# OMD_UWB.net
KiCad netlist of a schematic drawn in Altium Designer
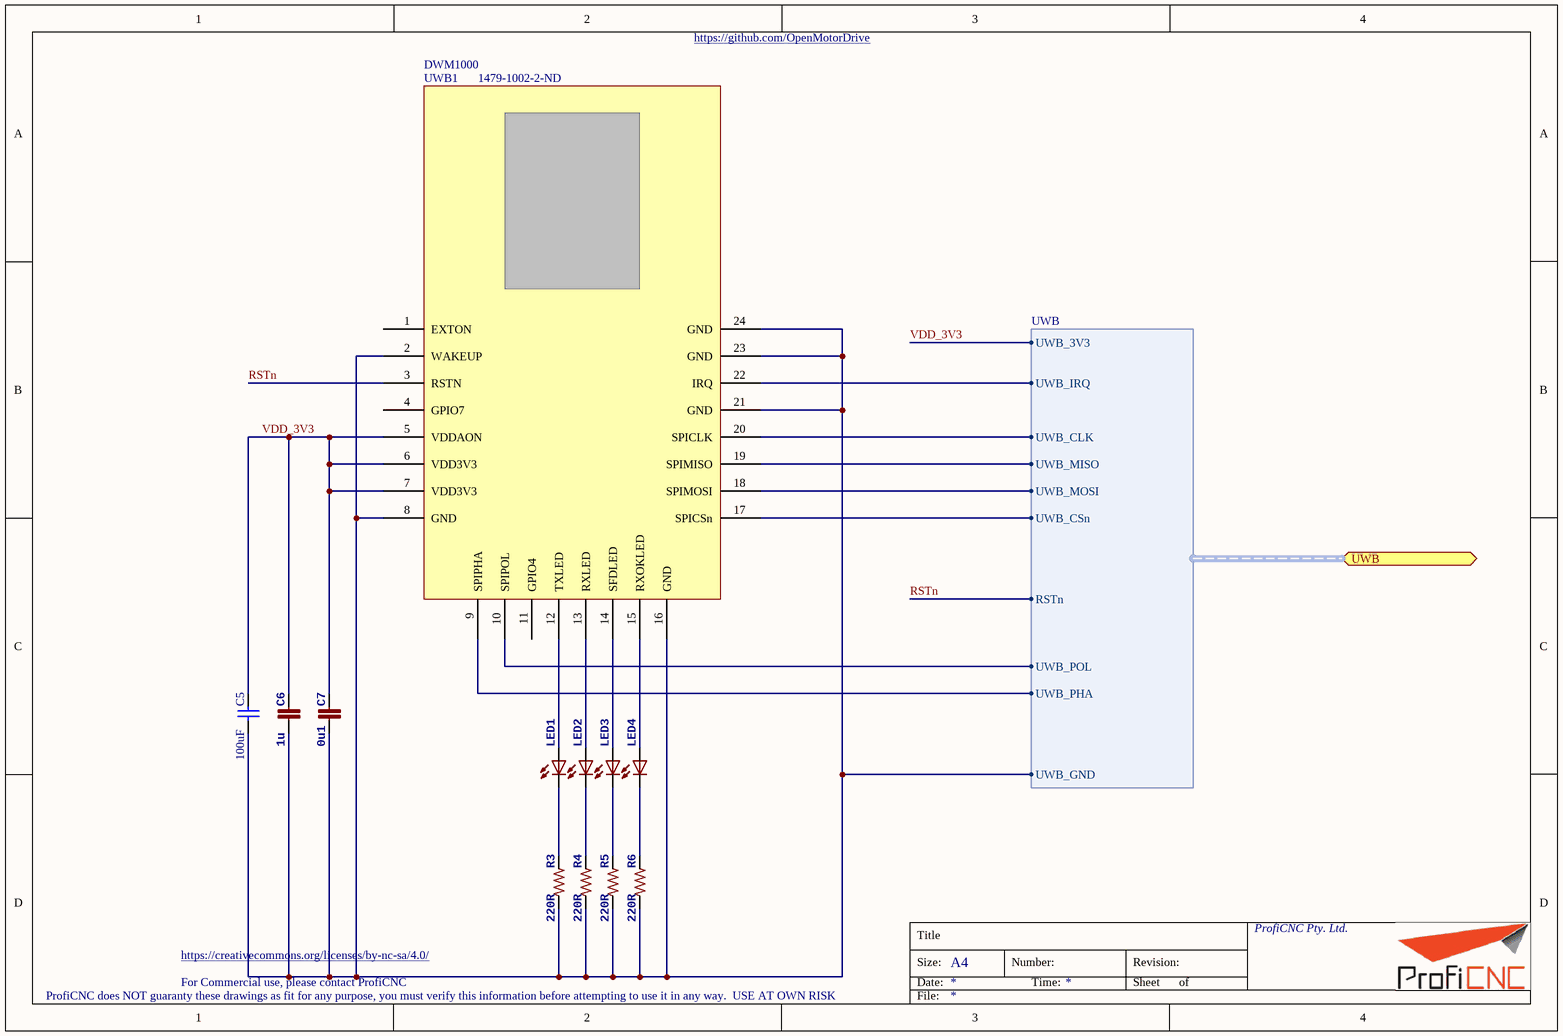
[diagram p0: OMD_UWB.SchDoc]

(export (version "E")
  (design (tool "Eeschema 10.0.6"))
  (components
    (comp (ref "C5")
      (value "100uF")
      (footprint "C0805")
      (fields (field (name "Comment") "GRM21BR60G107ME15L"))
      (libsource (lib "OMD") (part "Capacitor"))
    )
    (comp (ref "C6")
      (value "1u")
      (footprint "0201-cap")
      (description "CAP CER 1UF 6.3V X5R 0201")
      (libsource (lib "OMD") (part "CAP0603"))
    )
    (comp (ref "C7")
      (value "0u1")
      (footprint "0201-cap")
      (description "CAP CER 0.1UF 16V Y5V 0402")
      (libsource (lib "OMD") (part "CAP0402"))
    )
    (comp (ref "LED1")
      (value "AMBER")
      (footprint "0603-LED")
      (description "LED 1.6X0.8 DOME ORN CLEAR SMD")
      (libsource (lib "OMD") (part "LED0603"))
    )
    (comp (ref "LED2")
      (value "AMBER")
      (footprint "0603-LED")
      (description "LED 1.6X0.8 DOME ORN CLEAR SMD")
      (libsource (lib "OMD") (part "LED0603"))
    )
    (comp (ref "LED3")
      (value "AMBER")
      (footprint "0603-LED")
      (description "LED 1.6X0.8 DOME ORN CLEAR SMD")
      (libsource (lib "OMD") (part "LED0603"))
    )
    (comp (ref "LED4")
      (value "AMBER")
      (footprint "0603-LED")
      (description "LED 1.6X0.8 DOME ORN CLEAR SMD")
      (libsource (lib "OMD") (part "LED0603"))
    )
    (comp (ref "R3")
      (value "220R")
      (footprint "0402-RES")
      (description "RES 220 OHM 1/16W 1% 0402 SMD")
      (libsource (lib "OMD") (part "RESISTOR0402-RES"))
    )
    (comp (ref "R4")
      (value "220R")
      (footprint "0402-RES")
      (description "RES 220 OHM 1/16W 1% 0402 SMD")
      (libsource (lib "OMD") (part "RESISTOR0402-RES"))
    )
    (comp (ref "R5")
      (value "220R")
      (footprint "0402-RES")
      (description "RES 220 OHM 1/16W 1% 0402 SMD")
      (libsource (lib "OMD") (part "RESISTOR0402-RES"))
    )
    (comp (ref "R6")
      (value "220R")
      (footprint "0402-RES")
      (description "RES 220 OHM 1/16W 1% 0402 SMD")
      (libsource (lib "OMD") (part "RESISTOR0402-RES"))
    )
    (comp (ref "UWB1")
      (value "DWM1000")
      (footprint "DWM1000")
      (fields (field (name "SUPPLIER PART NUMBER 1") "1479-1002-2-ND"))
      (libsource (lib "OMD") (part "DWM1000"))
    )
  )
  (nets
    (net (code "2") (name "/RSTn") (class "Default")
      (node (ref "UWB1") (pin "3") (pinfunction "RSTN_3") (pintype "passive"))
    )
    (net (code "3") (name "/UWB_CLK") (class "Default")
      (node (ref "UWB1") (pin "20") (pinfunction "SPICLK_20") (pintype "passive"))
    )
    (net (code "4") (name "/UWB_CSn") (class "Default")
      (node (ref "UWB1") (pin "17") (pinfunction "SPICSn_17") (pintype "passive"))
    )
    (net (code "5") (name "/UWB_GND") (class "Default")
      (node (ref "C5") (pin "1") (pinfunction "1_1") (pintype "passive"))
      (node (ref "C6") (pin "2") (pinfunction "2_2") (pintype "passive"))
      (node (ref "C7") (pin "2") (pinfunction "2_2") (pintype "passive"))
      (node (ref "R3") (pin "1") (pinfunction "1_1") (pintype "passive"))
      (node (ref "R4") (pin "1") (pinfunction "1_1") (pintype "passive"))
      (node (ref "R5") (pin "1") (pinfunction "1_1") (pintype "passive"))
      (node (ref "R6") (pin "1") (pinfunction "1_1") (pintype "passive"))
      (node (ref "UWB1") (pin "16") (pinfunction "GND_16") (pintype "passive"))
      (node (ref "UWB1") (pin "2") (pinfunction "WAKEUP_2") (pintype "passive"))
      (node (ref "UWB1") (pin "21") (pinfunction "GND_21") (pintype "passive"))
      (node (ref "UWB1") (pin "23") (pinfunction "GND_23") (pintype "passive"))
      (node (ref "UWB1") (pin "24") (pinfunction "GND_24") (pintype "passive"))
      (node (ref "UWB1") (pin "8") (pinfunction "GND_8") (pintype "passive"))
    )
    (net (code "6") (name "/UWB_IRQ") (class "Default")
      (node (ref "UWB1") (pin "22") (pinfunction "IRQ_22") (pintype "passive"))
    )
    (net (code "7") (name "/UWB_MISO") (class "Default")
      (node (ref "UWB1") (pin "19") (pinfunction "SPIMISO_19") (pintype "passive"))
    )
    (net (code "8") (name "/UWB_MOSI") (class "Default")
      (node (ref "UWB1") (pin "18") (pinfunction "SPIMOSI_18") (pintype "passive"))
    )
    (net (code "9") (name "/UWB_PHA") (class "Default")
      (node (ref "UWB1") (pin "9") (pinfunction "SPIPHA_9") (pintype "passive"))
    )
    (net (code "10") (name "/UWB_POL") (class "Default")
      (node (ref "UWB1") (pin "10") (pinfunction "SPIPOL_10") (pintype "passive"))
    )
    (net (code "11") (name "/VDD_3V3") (class "Default")
      (node (ref "C5") (pin "2") (pinfunction "2_2") (pintype "passive"))
      (node (ref "C6") (pin "1") (pinfunction "1_1") (pintype "passive"))
      (node (ref "C7") (pin "1") (pinfunction "1_1") (pintype "passive"))
      (node (ref "UWB1") (pin "5") (pinfunction "VDDAON_5") (pintype "passive"))
      (node (ref "UWB1") (pin "6") (pinfunction "VDD3V3_6") (pintype "passive"))
      (node (ref "UWB1") (pin "7") (pinfunction "VDD3V3_7") (pintype "passive"))
    )
    (net (code "13") (name "Net-(LED1-PadC)") (class "Default")
      (node (ref "LED1") (pin "C") (pinfunction "C_C") (pintype "passive"))
      (node (ref "R3") (pin "2") (pinfunction "2_2") (pintype "passive"))
    )
    (net (code "14") (name "Net-(LED2-PadC)") (class "Default")
      (node (ref "LED2") (pin "C") (pinfunction "C_C") (pintype "passive"))
      (node (ref "R4") (pin "2") (pinfunction "2_2") (pintype "passive"))
    )
    (net (code "15") (name "Net-(LED3-PadC)") (class "Default")
      (node (ref "LED3") (pin "C") (pinfunction "C_C") (pintype "passive"))
      (node (ref "R5") (pin "2") (pinfunction "2_2") (pintype "passive"))
    )
    (net (code "16") (name "Net-(LED4-PadC)") (class "Default")
      (node (ref "LED4") (pin "C") (pinfunction "C_C") (pintype "passive"))
      (node (ref "R6") (pin "2") (pinfunction "2_2") (pintype "passive"))
    )
    (net (code "17") (name "Net-(UWB1-RXLED)") (class "Default")
      (node (ref "LED2") (pin "A") (pinfunction "A_A") (pintype "passive"))
      (node (ref "UWB1") (pin "13") (pinfunction "RXLED_13") (pintype "passive"))
    )
    (net (code "18") (name "Net-(UWB1-RXOKLED)") (class "Default")
      (node (ref "LED4") (pin "A") (pinfunction "A_A") (pintype "passive"))
      (node (ref "UWB1") (pin "15") (pinfunction "RXOKLED_15") (pintype "passive"))
    )
    (net (code "19") (name "Net-(UWB1-SFDLED)") (class "Default")
      (node (ref "LED3") (pin "A") (pinfunction "A_A") (pintype "passive"))
      (node (ref "UWB1") (pin "14") (pinfunction "SFDLED_14") (pintype "passive"))
    )
    (net (code "20") (name "Net-(UWB1-TXLED)") (class "Default")
      (node (ref "LED1") (pin "A") (pinfunction "A_A") (pintype "passive"))
      (node (ref "UWB1") (pin "12") (pinfunction "TXLED_12") (pintype "passive"))
    )
    (net (code "21") (name "unconnected-(UWB1-EXTON-Pad1)") (class "Default")
      (node (ref "UWB1") (pin "1") (pinfunction "EXTON_1") (pintype "passive"))
    )
    (net (code "22") (name "unconnected-(UWB1-GPIO4-Pad11)") (class "Default")
      (node (ref "UWB1") (pin "11") (pinfunction "GPIO4_11") (pintype "passive"))
    )
    (net (code "23") (name "unconnected-(UWB1-GPIO7-Pad4)") (class "Default")
      (node (ref "UWB1") (pin "4") (pinfunction "GPIO7_4") (pintype "passive"))
    )
  )
)
